# BattVoltageLevelDetector.net
KiCad netlist of a schematic drawn in Altium Designer
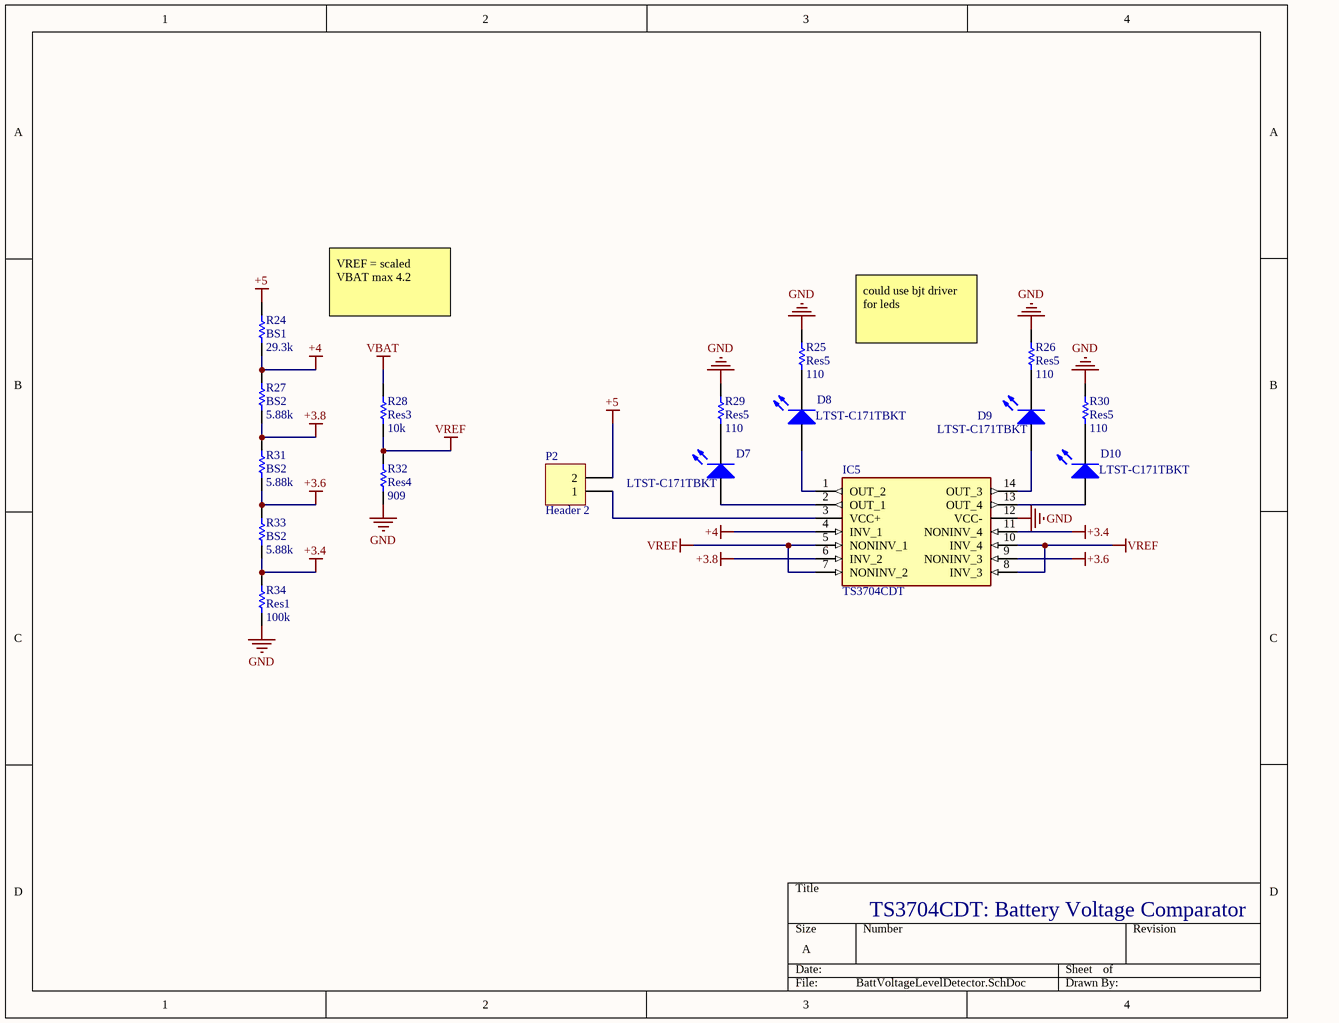
[diagram p0: BattVoltageLevelDetector.SchDoc]

(export (version "E")
  (design (tool "Eeschema 10.0.6"))
  (components
    (comp (ref "D7")
      (value "LTST-C171TBKT")
      (footprint "0402")
      (description "LED BLUE CLEAR CHIP SMD")
      (libsource (lib "Miscellaneous Devices") (part "LED0"))
    )
    (comp (ref "D8")
      (value "LTST-C171TBKT")
      (footprint "0402")
      (description "LED BLUE CLEAR CHIP SMD")
      (libsource (lib "Miscellaneous Devices") (part "LED0"))
    )
    (comp (ref "D9")
      (value "LTST-C171TBKT")
      (footprint "0402")
      (description "LED BLUE CLEAR CHIP SMD")
      (libsource (lib "Miscellaneous Devices") (part "LED0"))
    )
    (comp (ref "D10")
      (value "LTST-C171TBKT")
      (footprint "0402")
      (description "LED BLUE CLEAR CHIP SMD")
      (libsource (lib "Miscellaneous Devices") (part "LED0"))
    )
    (comp (ref "IC5")
      (value "TS3704CDT")
      (footprint "SOIC127P600X175-14N")
      (description "Integrated Circuit")
      (fields (field (name "MOUSER PART NUMBER") "511-TS3704CDT") (field (name "RS PART NUMBER") "8805496P"))
      (libsource (lib "*") (part "TS3704CDT"))
    )
    (comp (ref "P2")
      (value "Header 2")
      (footprint "HDR1X2")
      (description "Header, 2-Pin")
      (fields (field (name "PUBLISHER") "Altium Limited"))
      (libsource (lib "Miscellaneous Connectors") (part "Header 2"))
    )
    (comp (ref "R24")
      (value "BS1")
      (footprint "0402")
      (description "Resistor")
      (fields (field (name "ALTIUM_VALUE") "29.3k") (field (name "PUBLISHER") "Altium Limited"))
      (libsource (lib "Miscellaneous Devices") (part "Res1"))
    )
    (comp (ref "R25")
      (value "Res5")
      (footprint "0402")
      (description "Resistor")
      (fields (field (name "ALTIUM_VALUE") "110") (field (name "PUBLISHER") "Altium Limited"))
      (libsource (lib "Miscellaneous Devices") (part "Res1"))
    )
    (comp (ref "R26")
      (value "Res5")
      (footprint "0402")
      (description "Resistor")
      (fields (field (name "ALTIUM_VALUE") "110") (field (name "PUBLISHER") "Altium Limited"))
      (libsource (lib "Miscellaneous Devices") (part "Res1"))
    )
    (comp (ref "R27")
      (value "BS2")
      (footprint "0402")
      (description "Resistor")
      (fields (field (name "ALTIUM_VALUE") "5.88k") (field (name "PUBLISHER") "Altium Limited"))
      (libsource (lib "Miscellaneous Devices") (part "Res1"))
    )
    (comp (ref "R28")
      (value "Res3")
      (footprint "0402")
      (description "Resistor")
      (fields (field (name "ALTIUM_VALUE") "10k") (field (name "PUBLISHER") "Altium Limited"))
      (libsource (lib "Miscellaneous Devices") (part "Res1"))
    )
    (comp (ref "R29")
      (value "Res5")
      (footprint "0402")
      (description "Resistor")
      (fields (field (name "ALTIUM_VALUE") "110") (field (name "PUBLISHER") "Altium Limited"))
      (libsource (lib "Miscellaneous Devices") (part "Res1"))
    )
    (comp (ref "R30")
      (value "Res5")
      (footprint "0402")
      (description "Resistor")
      (fields (field (name "ALTIUM_VALUE") "110") (field (name "PUBLISHER") "Altium Limited"))
      (libsource (lib "Miscellaneous Devices") (part "Res1"))
    )
    (comp (ref "R31")
      (value "BS2")
      (footprint "0402")
      (description "Resistor")
      (fields (field (name "ALTIUM_VALUE") "5.88k") (field (name "PUBLISHER") "Altium Limited"))
      (libsource (lib "Miscellaneous Devices") (part "Res1"))
    )
    (comp (ref "R32")
      (value "Res4")
      (footprint "0402")
      (description "Resistor")
      (fields (field (name "ALTIUM_VALUE") "909") (field (name "PUBLISHER") "Altium Limited"))
      (libsource (lib "Miscellaneous Devices") (part "Res1"))
    )
    (comp (ref "R33")
      (value "BS2")
      (footprint "0402")
      (description "Resistor")
      (fields (field (name "ALTIUM_VALUE") "5.88k") (field (name "PUBLISHER") "Altium Limited"))
      (libsource (lib "Miscellaneous Devices") (part "Res1"))
    )
    (comp (ref "R34")
      (value "Res1")
      (footprint "0402")
      (description "Resistor")
      (fields (field (name "ALTIUM_VALUE") "100k") (field (name "PUBLISHER") "Altium Limited"))
      (libsource (lib "Miscellaneous Devices") (part "Res1"))
    )
  )
  (nets
    (net (code "1") (name "+3.4") (class "Default")
      (node (ref "IC5") (pin "11") (pinfunction "NONINV_4_11") (pintype "input"))
      (node (ref "R33") (pin "1") (pinfunction "1_1") (pintype "passive"))
      (node (ref "R34") (pin "2") (pinfunction "2_2") (pintype "passive"))
    )
    (net (code "2") (name "+3.6") (class "Default")
      (node (ref "IC5") (pin "9") (pinfunction "NONINV_3_9") (pintype "input"))
      (node (ref "R31") (pin "1") (pinfunction "1_1") (pintype "passive"))
      (node (ref "R33") (pin "2") (pinfunction "2_2") (pintype "passive"))
    )
    (net (code "3") (name "+3.8") (class "Default")
      (node (ref "IC5") (pin "6") (pinfunction "INV_2_6") (pintype "input"))
      (node (ref "R27") (pin "1") (pinfunction "1_1") (pintype "passive"))
      (node (ref "R31") (pin "2") (pinfunction "2_2") (pintype "passive"))
    )
    (net (code "4") (name "+4") (class "Default")
      (node (ref "IC5") (pin "4") (pinfunction "INV_1_4") (pintype "input"))
      (node (ref "R24") (pin "1") (pinfunction "1_1") (pintype "passive"))
      (node (ref "R27") (pin "2") (pinfunction "2_2") (pintype "passive"))
    )
    (net (code "5") (name "+5") (class "Default")
      (node (ref "P2") (pin "2") (pinfunction "2_2") (pintype "passive"))
      (node (ref "R24") (pin "2") (pinfunction "2_2") (pintype "passive"))
    )
    (net (code "6") (name "GND") (class "Default")
      (node (ref "IC5") (pin "12") (pinfunction "VCC-_12") (pintype "power_in"))
      (node (ref "R25") (pin "2") (pinfunction "2_2") (pintype "passive"))
      (node (ref "R26") (pin "2") (pinfunction "2_2") (pintype "passive"))
      (node (ref "R29") (pin "2") (pinfunction "2_2") (pintype "passive"))
      (node (ref "R30") (pin "2") (pinfunction "2_2") (pintype "passive"))
      (node (ref "R32") (pin "1") (pinfunction "1_1") (pintype "passive"))
      (node (ref "R34") (pin "1") (pinfunction "1_1") (pintype "passive"))
    )
    (net (code "7") (name "Net-(D7-A)") (class "Default")
      (node (ref "D7") (pin "1") (pinfunction "A_1") (pintype "passive"))
      (node (ref "IC5") (pin "2") (pinfunction "OUT_1_2") (pintype "output"))
    )
    (net (code "8") (name "Net-(D7-K)") (class "Default")
      (node (ref "D7") (pin "2") (pinfunction "K_2") (pintype "passive"))
      (node (ref "R29") (pin "1") (pinfunction "1_1") (pintype "passive"))
    )
    (net (code "9") (name "Net-(D8-A)") (class "Default")
      (node (ref "D8") (pin "1") (pinfunction "A_1") (pintype "passive"))
      (node (ref "IC5") (pin "1") (pinfunction "OUT_2_1") (pintype "output"))
    )
    (net (code "10") (name "Net-(D8-K)") (class "Default")
      (node (ref "D8") (pin "2") (pinfunction "K_2") (pintype "passive"))
      (node (ref "R25") (pin "1") (pinfunction "1_1") (pintype "passive"))
    )
    (net (code "11") (name "Net-(D9-A)") (class "Default")
      (node (ref "D9") (pin "1") (pinfunction "A_1") (pintype "passive"))
      (node (ref "IC5") (pin "14") (pinfunction "OUT_3_14") (pintype "output"))
    )
    (net (code "12") (name "Net-(D9-K)") (class "Default")
      (node (ref "D9") (pin "2") (pinfunction "K_2") (pintype "passive"))
      (node (ref "R26") (pin "1") (pinfunction "1_1") (pintype "passive"))
    )
    (net (code "13") (name "Net-(D10-A)") (class "Default")
      (node (ref "D10") (pin "1") (pinfunction "A_1") (pintype "passive"))
      (node (ref "IC5") (pin "13") (pinfunction "OUT_4_13") (pintype "output"))
    )
    (net (code "14") (name "Net-(D10-K)") (class "Default")
      (node (ref "D10") (pin "2") (pinfunction "K_2") (pintype "passive"))
      (node (ref "R30") (pin "1") (pinfunction "1_1") (pintype "passive"))
    )
    (net (code "15") (name "Net-(IC5-VCC+)") (class "Default")
      (node (ref "IC5") (pin "3") (pinfunction "VCC+_3") (pintype "power_in"))
      (node (ref "P2") (pin "1") (pinfunction "1_1") (pintype "passive"))
    )
    (net (code "16") (name "VBAT") (class "Default")
      (node (ref "R28") (pin "2") (pinfunction "2_2") (pintype "passive"))
    )
    (net (code "17") (name "VREF") (class "Default")
      (node (ref "IC5") (pin "10") (pinfunction "INV_4_10") (pintype "input"))
      (node (ref "IC5") (pin "5") (pinfunction "NONINV_1_5") (pintype "input"))
      (node (ref "IC5") (pin "7") (pinfunction "NONINV_2_7") (pintype "input"))
      (node (ref "IC5") (pin "8") (pinfunction "INV_3_8") (pintype "input"))
      (node (ref "R28") (pin "1") (pinfunction "1_1") (pintype "passive"))
      (node (ref "R32") (pin "2") (pinfunction "2_2") (pintype "passive"))
    )
  )
)
